# Baselli.net
KiCad netlist of a schematic drawn in EAGLE
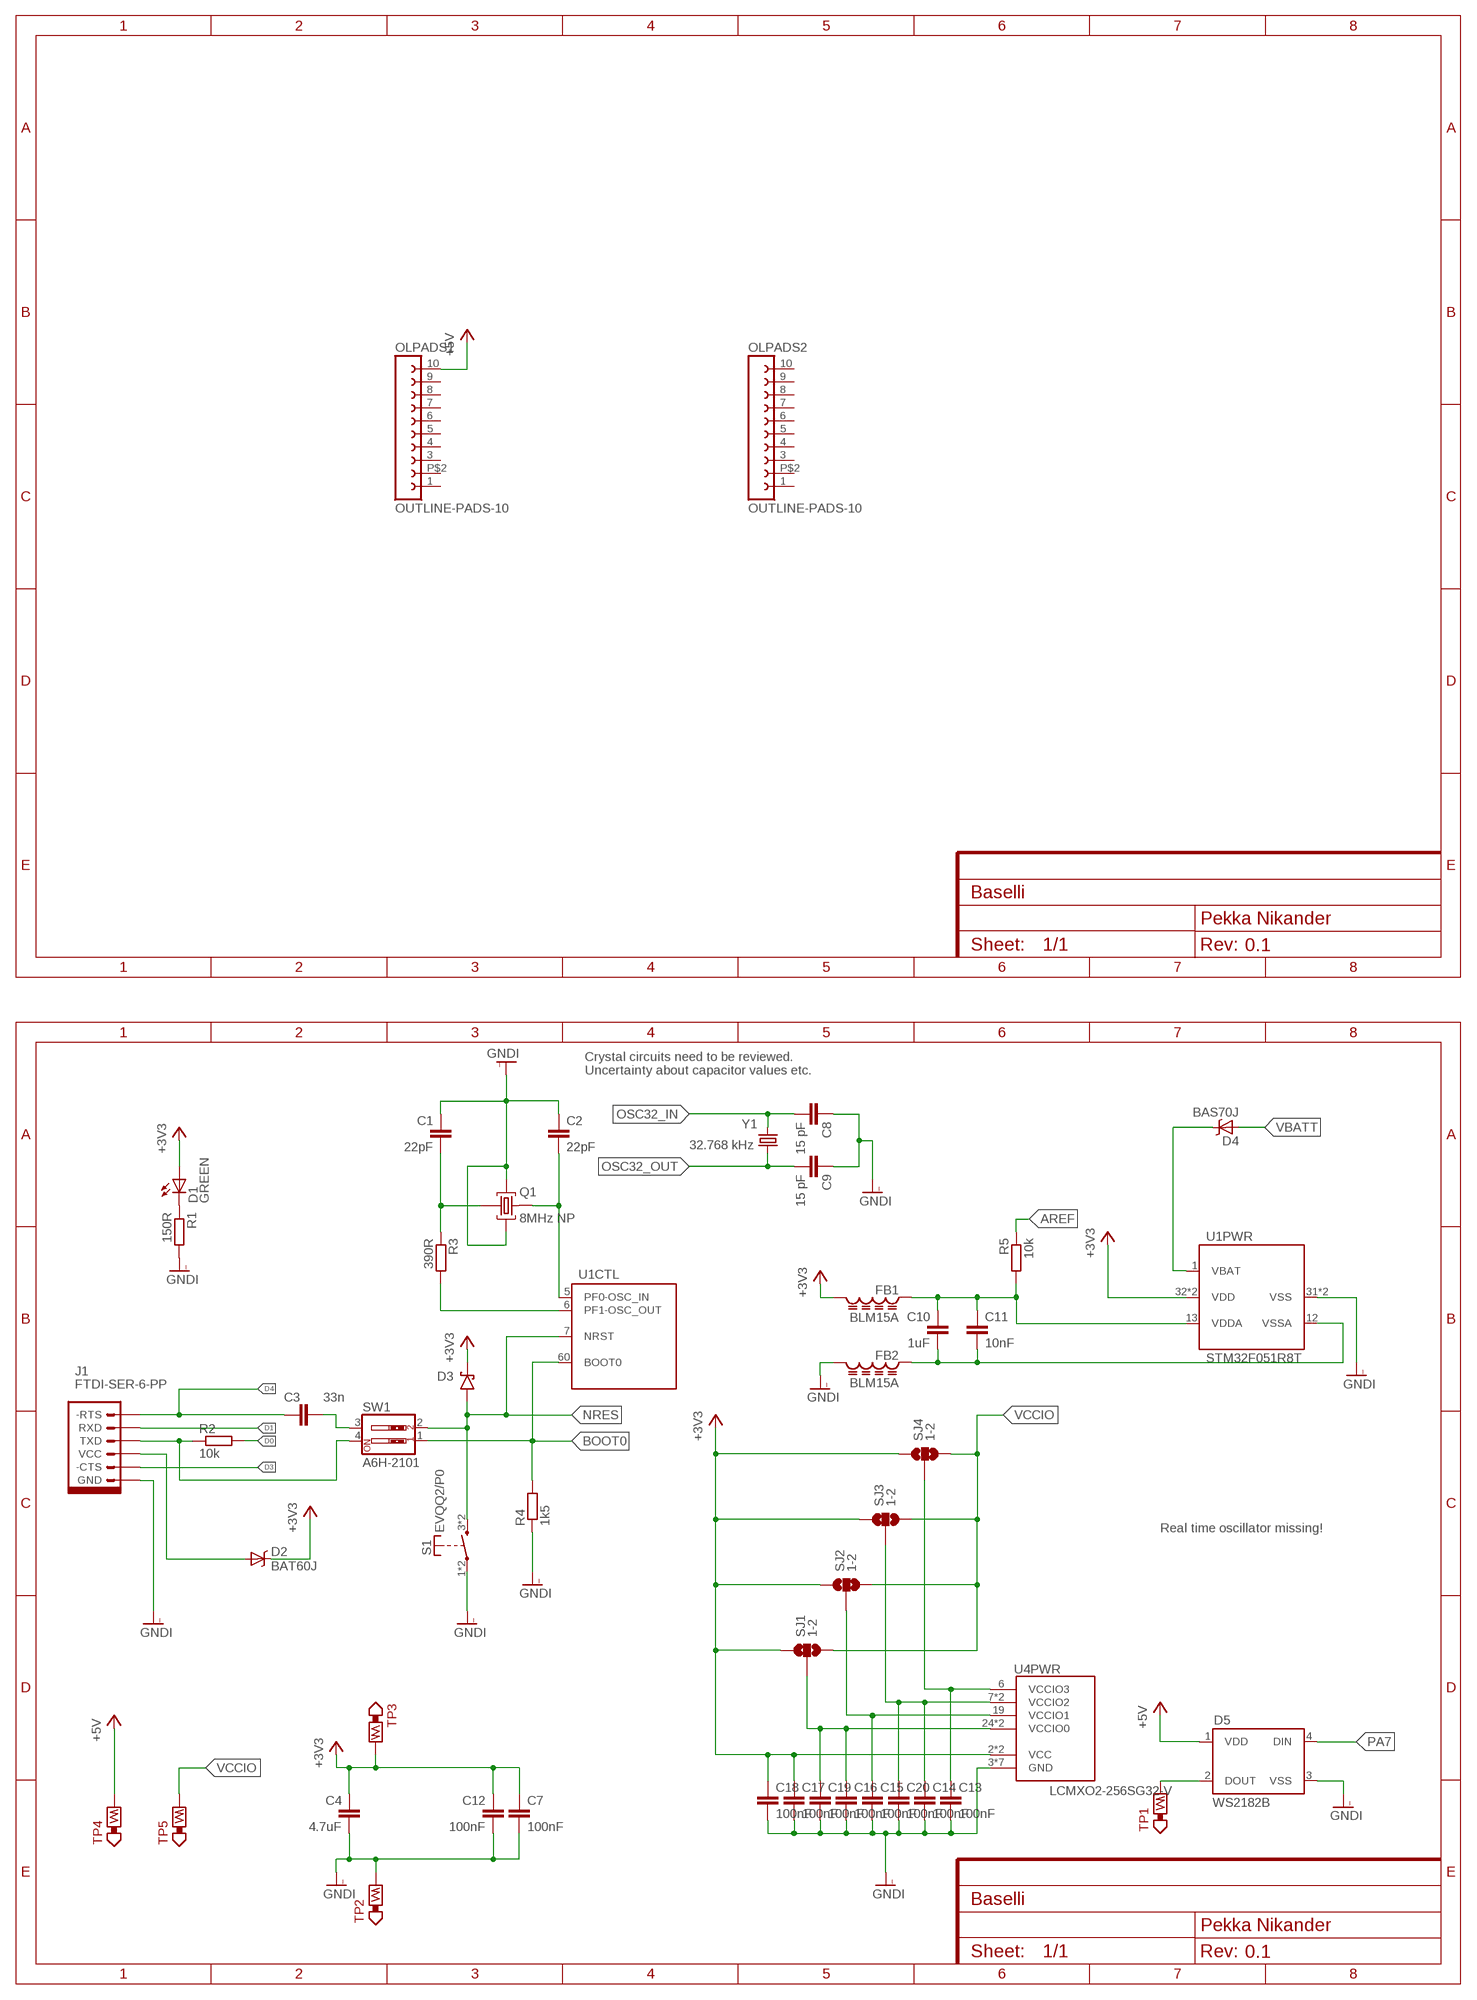
[diagram p0: schematic, sheet 1, part 1 of 2]
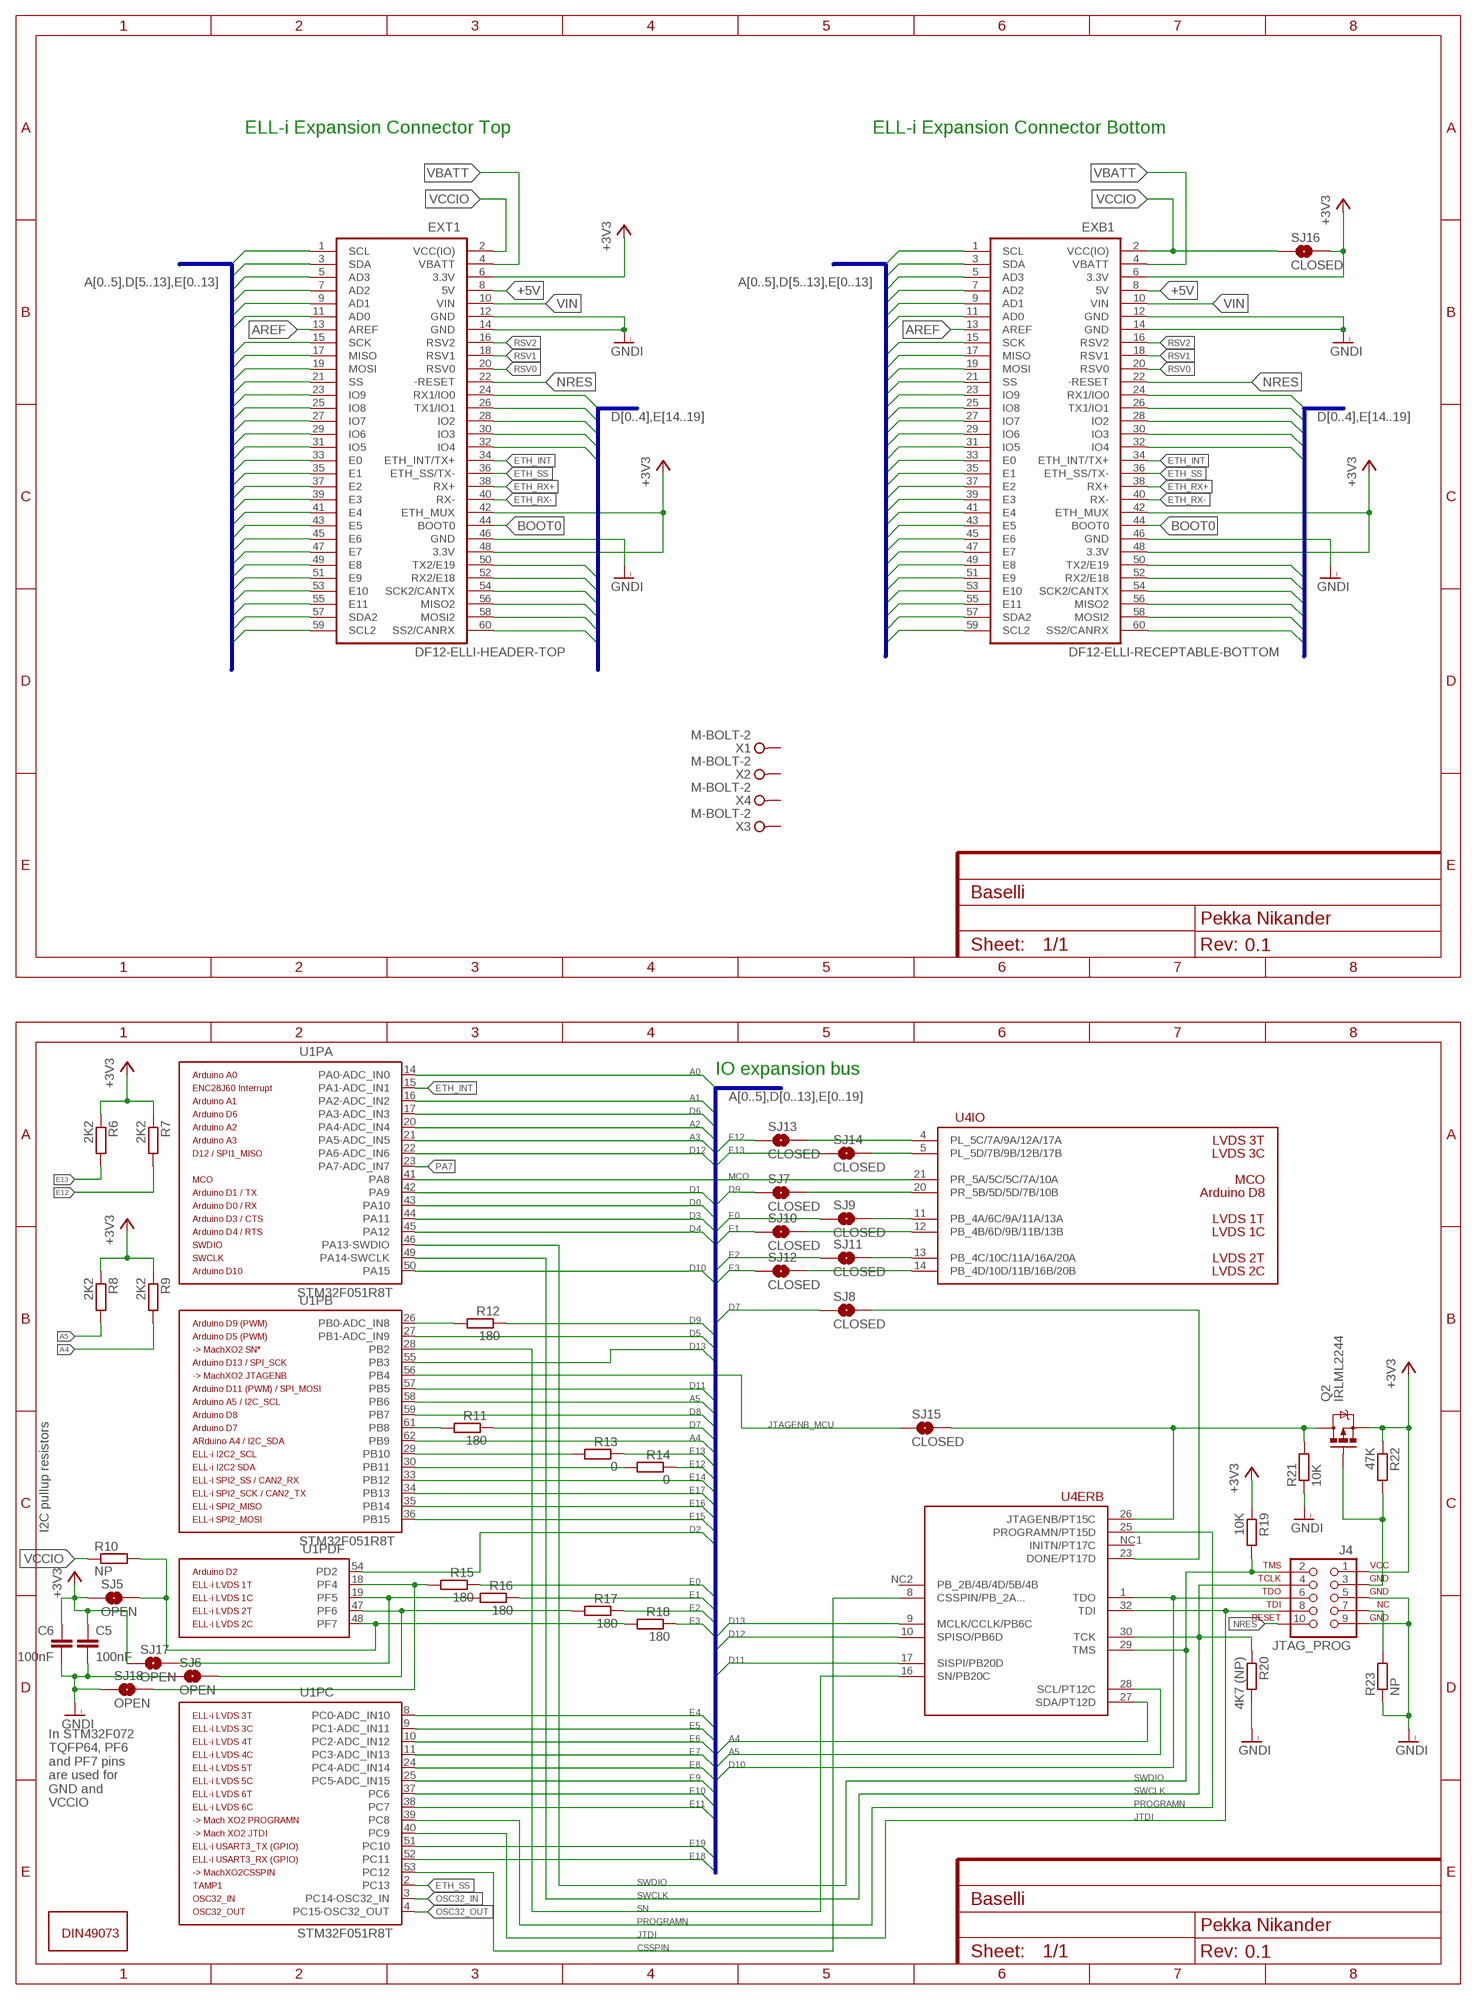
[diagram p1: schematic, sheet 1, part 2 of 2]

(export (version "E")
  (design (tool "Eeschema 10.0.6"))
  (components
    (comp (ref "C1")
      (value "22pF")
      (footprint "eagle-import:C0402")
      (libsource (lib "eagle-import") (part "C0402"))
    )
    (comp (ref "C2")
      (value "22pF")
      (footprint "eagle-import:C0402")
      (libsource (lib "eagle-import") (part "C0402"))
    )
    (comp (ref "C3")
      (value "33n")
      (footprint "eagle-import:C0402")
      (libsource (lib "eagle-import") (part "C0402"))
    )
    (comp (ref "C4")
      (value "4.7uF")
      (footprint "eagle-import:C0402")
      (libsource (lib "eagle-import") (part "C0402"))
    )
    (comp (ref "C5")
      (value "100nF")
      (footprint "eagle-import:C0402")
      (libsource (lib "eagle-import") (part "C0402"))
    )
    (comp (ref "C6")
      (value "100nF")
      (footprint "eagle-import:C0402")
      (libsource (lib "eagle-import") (part "C0402"))
    )
    (comp (ref "C7")
      (value "100nF")
      (footprint "eagle-import:C0402")
      (libsource (lib "eagle-import") (part "C0402"))
    )
    (comp (ref "C8")
      (value "15 pF")
      (footprint "eagle-import:C0402")
      (libsource (lib "eagle-import") (part "C0402"))
    )
    (comp (ref "C9")
      (value "15 pF")
      (footprint "eagle-import:C0402")
      (libsource (lib "eagle-import") (part "C0402"))
    )
    (comp (ref "C10")
      (value "1uF")
      (footprint "eagle-import:C0402")
      (libsource (lib "eagle-import") (part "C0402"))
    )
    (comp (ref "C11")
      (value "10nF")
      (footprint "eagle-import:C0402")
      (libsource (lib "eagle-import") (part "C0402"))
    )
    (comp (ref "C12")
      (value "100nF")
      (footprint "eagle-import:C0402")
      (libsource (lib "eagle-import") (part "C0402"))
    )
    (comp (ref "C13")
      (value "100nF")
      (footprint "eagle-import:C0402")
      (libsource (lib "eagle-import") (part "C0402"))
    )
    (comp (ref "C14")
      (value "100nF")
      (footprint "eagle-import:C0402")
      (libsource (lib "eagle-import") (part "C0402"))
    )
    (comp (ref "C15")
      (value "100nF")
      (footprint "eagle-import:C0402")
      (libsource (lib "eagle-import") (part "C0402"))
    )
    (comp (ref "C16")
      (value "100nF")
      (footprint "eagle-import:C0402")
      (libsource (lib "eagle-import") (part "C0402"))
    )
    (comp (ref "C17")
      (value "100nF")
      (footprint "eagle-import:C0402")
      (libsource (lib "eagle-import") (part "C0402"))
    )
    (comp (ref "C18")
      (value "100nF")
      (footprint "eagle-import:C0402")
      (libsource (lib "eagle-import") (part "C0402"))
    )
    (comp (ref "C19")
      (value "100nF")
      (footprint "eagle-import:C0402")
      (libsource (lib "eagle-import") (part "C0402"))
    )
    (comp (ref "C20")
      (value "100nF")
      (footprint "eagle-import:C0402")
      (libsource (lib "eagle-import") (part "C0402"))
    )
    (comp (ref "D1")
      (value "GREEN")
      (footprint "eagle-import:LED-0603")
      (libsource (lib "eagle-import") (part "LED-GREEN0603"))
    )
    (comp (ref "D2")
      (value "BAT60J")
      (footprint "eagle-import:SOD-323")
      (libsource (lib "eagle-import") (part "DIODE-SCHOTTKY-BAT60J"))
    )
    (comp (ref "D3")
      (value "BAT60J")
      (footprint "eagle-import:SOD323_DIODE")
      (libsource (lib "eagle-import") (part "BAT60J"))
    )
    (comp (ref "D4")
      (value "BAS70J")
      (footprint "eagle-import:SOD-323")
      (libsource (lib "eagle-import") (part "BAS70J"))
    )
    (comp (ref "D5")
      (value "WS2182B")
      (footprint "eagle-import:WS2812B")
      (libsource (lib "eagle-import") (part "WS2812B"))
    )
    (comp (ref "DIMENSIONS1")
      (value "DIN49073-OUTLINE")
      (footprint "eagle-import:DIN49073-1_2010-02-OUTLINE")
      (libsource (lib "eagle-import") (part "DIN49073-OUTLINE"))
    )
    (comp (ref "EXB1")
      (value "DF12-ELLI-RECEPTABLE-BOTTOM")
      (footprint "eagle-import:DF12-60DS-0.5V")
      (libsource (lib "eagle-import") (part "DF12-ELLI-RECEPTABLE-BOTTOM"))
    )
    (comp (ref "EXT1")
      (value "DF12-ELLI-HEADER-TOP")
      (footprint "eagle-import:DF12(4.0)-60DP-0.5V")
      (libsource (lib "eagle-import") (part "DF12-ELLI-HEADER-TOP"))
    )
    (comp (ref "FB1")
      (value "BLM15A")
      (footprint "eagle-import:0402")
      (libsource (lib "eagle-import") (part "LQM15"))
    )
    (comp (ref "FB2")
      (value "BLM15A")
      (footprint "eagle-import:0402")
      (libsource (lib "eagle-import") (part "LQM15"))
    )
    (comp (ref "J1")
      (value "FTDI-SER-6-PP")
      (footprint "eagle-import:FTDI-SER-6-SIL")
      (libsource (lib "eagle-import") (part "FTDI-SER-6-PP"))
    )
    (comp (ref "J4")
      (value "JTAG_PROG")
      (footprint "eagle-import:CLP-105-02-X-D")
      (libsource (lib "eagle-import") (part "JTAG_PROG"))
    )
    (comp (ref "OLPADS1")
      (value "OUTLINE-PADS-10")
      (footprint "eagle-import:DIN49073-1_2010-02-PADS-10")
      (libsource (lib "eagle-import") (part "OUTLINE-PADS-10"))
    )
    (comp (ref "OLPADS2")
      (value "OUTLINE-PADS-10")
      (footprint "eagle-import:DIN49073-1_2010-02-PADS-10")
      (libsource (lib "eagle-import") (part "OUTLINE-PADS-10"))
    )
    (comp (ref "Q1")
      (value "8MHz NP")
      (footprint "eagle-import:CRYSTAL-SMD-3225-GND")
      (libsource (lib "eagle-import") (part "CRYSTAL_WITH_GND"))
    )
    (comp (ref "Q2")
      (value "IRLML2244")
      (footprint "eagle-import:SOT23-3")
      (libsource (lib "eagle-import") (part "MOSFET-PCHANNELIRLML2244"))
    )
    (comp (ref "R1")
      (value "150R")
      (footprint "eagle-import:R0402")
      (libsource (lib "eagle-import") (part "R0402"))
    )
    (comp (ref "R2")
      (value "10k")
      (footprint "eagle-import:R0402")
      (libsource (lib "eagle-import") (part "R0402"))
    )
    (comp (ref "R3")
      (value "390R")
      (footprint "eagle-import:R0402")
      (libsource (lib "eagle-import") (part "R0402"))
    )
    (comp (ref "R4")
      (value "1k5")
      (footprint "eagle-import:R0402")
      (libsource (lib "eagle-import") (part "R0402"))
    )
    (comp (ref "R5")
      (value "10k")
      (footprint "eagle-import:R0805")
      (libsource (lib "eagle-import") (part "R0805"))
    )
    (comp (ref "R6")
      (value "2K2")
      (footprint "eagle-import:R0402")
      (libsource (lib "eagle-import") (part "R0402"))
    )
    (comp (ref "R7")
      (value "2K2")
      (footprint "eagle-import:R0402")
      (libsource (lib "eagle-import") (part "R0402"))
    )
    (comp (ref "R8")
      (value "2K2")
      (footprint "eagle-import:R0402")
      (libsource (lib "eagle-import") (part "R0402"))
    )
    (comp (ref "R9")
      (value "2K2")
      (footprint "eagle-import:R0402")
      (libsource (lib "eagle-import") (part "R0402"))
    )
    (comp (ref "R10")
      (value "NP")
      (footprint "eagle-import:R0805")
      (libsource (lib "eagle-import") (part "R0805"))
    )
    (comp (ref "R11")
      (value "180")
      (footprint "eagle-import:R0805")
      (libsource (lib "eagle-import") (part "R0805"))
    )
    (comp (ref "R12")
      (value "180")
      (footprint "eagle-import:R0805")
      (libsource (lib "eagle-import") (part "R0805"))
    )
    (comp (ref "R13")
      (value "0")
      (footprint "eagle-import:R0805")
      (libsource (lib "eagle-import") (part "R0805"))
    )
    (comp (ref "R14")
      (value "0")
      (footprint "eagle-import:R0805")
      (libsource (lib "eagle-import") (part "R0805"))
    )
    (comp (ref "R15")
      (value "180")
      (footprint "eagle-import:R0805")
      (libsource (lib "eagle-import") (part "R0805"))
    )
    (comp (ref "R16")
      (value "180")
      (footprint "eagle-import:R0805")
      (libsource (lib "eagle-import") (part "R0805"))
    )
    (comp (ref "R17")
      (value "180")
      (footprint "eagle-import:R0805")
      (libsource (lib "eagle-import") (part "R0805"))
    )
    (comp (ref "R18")
      (value "180")
      (footprint "eagle-import:R0805")
      (libsource (lib "eagle-import") (part "R0805"))
    )
    (comp (ref "R19")
      (value "10K")
      (footprint "eagle-import:R0402")
      (libsource (lib "eagle-import") (part "R0402"))
    )
    (comp (ref "R20")
      (value "4K7 (NP)")
      (footprint "eagle-import:R0603")
      (libsource (lib "eagle-import") (part "R0603"))
    )
    (comp (ref "R21")
      (value "10K")
      (footprint "eagle-import:R0402")
      (libsource (lib "eagle-import") (part "R0402"))
    )
    (comp (ref "R22")
      (value "47K")
      (footprint "eagle-import:R0402")
      (libsource (lib "eagle-import") (part "R0402"))
    )
    (comp (ref "R23")
      (value "NP")
      (footprint "eagle-import:R0805")
      (libsource (lib "eagle-import") (part "R0805"))
    )
    (comp (ref "S1")
      (value "EVQQ2/P0")
      (footprint "eagle-import:EVQQ2_P0")
      (libsource (lib "eagle-import") (part "EVQQ2/P0"))
    )
    (comp (ref "SJ1")
      (value "1-2")
      (footprint "eagle-import:SJ_3_PASTE1&2")
      (libsource (lib "eagle-import") (part "SOLDERJUMPER_2WAYPASTE1&2"))
    )
    (comp (ref "SJ2")
      (value "1-2")
      (footprint "eagle-import:SJ_3_PASTE1&2")
      (libsource (lib "eagle-import") (part "SOLDERJUMPER_2WAYPASTE1&2"))
    )
    (comp (ref "SJ3")
      (value "1-2")
      (footprint "eagle-import:SJ_3_PASTE1&2")
      (libsource (lib "eagle-import") (part "SOLDERJUMPER_2WAYPASTE1&2"))
    )
    (comp (ref "SJ4")
      (value "1-2")
      (footprint "eagle-import:SJ_3_PASTE1&2")
      (libsource (lib "eagle-import") (part "SOLDERJUMPER_2WAYPASTE1&2"))
    )
    (comp (ref "SJ5")
      (value "OPEN")
      (footprint "eagle-import:SJ_2S-NO")
      (libsource (lib "eagle-import") (part "SOLDERJUMPERNO"))
    )
    (comp (ref "SJ6")
      (value "OPEN")
      (footprint "eagle-import:SJ_2S-NO")
      (libsource (lib "eagle-import") (part "SOLDERJUMPERNO"))
    )
    (comp (ref "SJ7")
      (value "CLOSED")
      (footprint "eagle-import:SJ_2S-TRACE")
      (libsource (lib "eagle-import") (part "SOLDERJUMPERTRACE"))
    )
    (comp (ref "SJ8")
      (value "CLOSED")
      (footprint "eagle-import:SJ_2S-TRACE")
      (libsource (lib "eagle-import") (part "SOLDERJUMPERTRACE"))
    )
    (comp (ref "SJ9")
      (value "CLOSED")
      (footprint "eagle-import:SJ_2S-TRACE")
      (libsource (lib "eagle-import") (part "SOLDERJUMPERTRACE"))
    )
    (comp (ref "SJ10")
      (value "CLOSED")
      (footprint "eagle-import:SJ_2S-TRACE")
      (libsource (lib "eagle-import") (part "SOLDERJUMPERTRACE"))
    )
    (comp (ref "SJ11")
      (value "CLOSED")
      (footprint "eagle-import:SJ_2S-TRACE")
      (libsource (lib "eagle-import") (part "SOLDERJUMPERTRACE"))
    )
    (comp (ref "SJ12")
      (value "CLOSED")
      (footprint "eagle-import:SJ_2S-TRACE")
      (libsource (lib "eagle-import") (part "SOLDERJUMPERTRACE"))
    )
    (comp (ref "SJ13")
      (value "CLOSED")
      (footprint "eagle-import:SJ_2S-TRACE")
      (libsource (lib "eagle-import") (part "SOLDERJUMPERTRACE"))
    )
    (comp (ref "SJ14")
      (value "CLOSED")
      (footprint "eagle-import:SJ_2S-TRACE")
      (libsource (lib "eagle-import") (part "SOLDERJUMPERTRACE"))
    )
    (comp (ref "SJ15")
      (value "CLOSED")
      (footprint "eagle-import:SJ_2S-TRACE")
      (libsource (lib "eagle-import") (part "SOLDERJUMPERTRACE"))
    )
    (comp (ref "SJ16")
      (value "CLOSED")
      (footprint "eagle-import:SJ_2S-TRACE")
      (libsource (lib "eagle-import") (part "SOLDERJUMPERTRACE"))
    )
    (comp (ref "SJ17")
      (value "OPEN")
      (footprint "eagle-import:SJ_2S-NO")
      (libsource (lib "eagle-import") (part "SOLDERJUMPERNO"))
    )
    (comp (ref "SJ18")
      (value "OPEN")
      (footprint "eagle-import:SJ_2S-NO")
      (libsource (lib "eagle-import") (part "SOLDERJUMPERNO"))
    )
    (comp (ref "SW1")
      (value "A6H-2101")
      (footprint "eagle-import:DIPSWITCH-02-50MIL")
      (libsource (lib "eagle-import") (part "SW_DIP-2-SMT-HALFSIZE"))
    )
    (comp (ref "TP1")
      (value "TEST_POINT-5000")
      (footprint "eagle-import:TP_5021")
      (libsource (lib "eagle-import") (part "TEST_POINT-5000"))
    )
    (comp (ref "TP2")
      (value "TEST_POINT-5000")
      (footprint "eagle-import:TP_5021")
      (libsource (lib "eagle-import") (part "TEST_POINT-5000"))
    )
    (comp (ref "TP3")
      (value "TEST_POINT-5000")
      (footprint "eagle-import:TP_5021")
      (libsource (lib "eagle-import") (part "TEST_POINT-5000"))
    )
    (comp (ref "TP4")
      (value "TEST_POINT-5000")
      (footprint "eagle-import:TP_5021")
      (libsource (lib "eagle-import") (part "TEST_POINT-5000"))
    )
    (comp (ref "TP5")
      (value "TEST_POINT-5000")
      (footprint "eagle-import:TP_5021")
      (libsource (lib "eagle-import") (part "TEST_POINT-5000"))
    )
    (comp (ref "U1")
      (value "STM32F051R8T")
      (footprint "eagle-import:LQFP64")
      (libsource (lib "eagle-import") (part "STM32F051RT8"))
    )
    (comp (ref "U4")
      (value "LCMXO2-256SG32-V")
      (footprint "eagle-import:QFN-32-PAD-VIAS")
      (libsource (lib "eagle-import") (part "LCMXO2-256SG32-V"))
    )
    (comp (ref "X1")
      (value "M-BOLT-2")
      (footprint "eagle-import:M2-1")
      (libsource (lib "eagle-import") (part "M-BOLT-2"))
    )
    (comp (ref "X2")
      (value "M-BOLT-2")
      (footprint "eagle-import:M2-1")
      (libsource (lib "eagle-import") (part "M-BOLT-2"))
    )
    (comp (ref "X3")
      (value "M-BOLT-2")
      (footprint "eagle-import:M2-1")
      (libsource (lib "eagle-import") (part "M-BOLT-2"))
    )
    (comp (ref "X4")
      (value "M-BOLT-2")
      (footprint "eagle-import:M2-1")
      (libsource (lib "eagle-import") (part "M-BOLT-2"))
    )
    (comp (ref "Y1")
      (value "32.768 kHz")
      (footprint "eagle-import:CRYSTAL-32KHZ-SMD")
      (libsource (lib "eagle-import") (part "CRYSTAL32-SMD"))
    )
  )
  (nets
    (net (code "1") (name "+3V3") (class "Default")
      (node (ref "C12") (pin "1") (pinfunction "1_1") (pintype "passive"))
      (node (ref "C17") (pin "1") (pinfunction "1_1") (pintype "passive"))
      (node (ref "C18") (pin "1") (pinfunction "1_1") (pintype "passive"))
      (node (ref "C4") (pin "1") (pinfunction "1_1") (pintype "passive"))
      (node (ref "C5") (pin "1") (pinfunction "1_1") (pintype "passive"))
      (node (ref "C6") (pin "1") (pinfunction "1_1") (pintype "passive"))
      (node (ref "C7") (pin "1") (pinfunction "1_1") (pintype "passive"))
      (node (ref "D1") (pin "A") (pinfunction "A_A") (pintype "passive"))
      (node (ref "D2") (pin "C") (pinfunction "C_C") (pintype "passive"))
      (node (ref "D3") (pin "1") (pinfunction "C_1") (pintype "passive"))
      (node (ref "EXB1") (pin "42") (pinfunction "ETH_MUX_42") (pintype "bidirectional"))
      (node (ref "EXB1") (pin "48") (pinfunction "3.3V_48") (pintype "bidirectional"))
      (node (ref "EXB1") (pin "6") (pinfunction "3.3V_6") (pintype "power_in"))
      (node (ref "EXT1") (pin "42") (pinfunction "ETH_MUX_42") (pintype "bidirectional"))
      (node (ref "EXT1") (pin "48") (pinfunction "3.3V_48") (pintype "bidirectional"))
      (node (ref "EXT1") (pin "6") (pinfunction "3.3V_6") (pintype "power_in"))
      (node (ref "FB1") (pin "2") (pinfunction "2_2") (pintype "passive"))
      (node (ref "J4") (pin "1") (pinfunction "1_1") (pintype "power_in"))
      (node (ref "Q2") (pin "2") (pinfunction "S_2") (pintype "passive"))
      (node (ref "R19") (pin "1") (pinfunction "1_1") (pintype "passive"))
      (node (ref "R22") (pin "1") (pinfunction "1_1") (pintype "passive"))
      (node (ref "R6") (pin "1") (pinfunction "1_1") (pintype "passive"))
      (node (ref "R7") (pin "1") (pinfunction "1_1") (pintype "passive"))
      (node (ref "R8") (pin "1") (pinfunction "1_1") (pintype "passive"))
      (node (ref "R9") (pin "1") (pinfunction "1_1") (pintype "passive"))
      (node (ref "SJ1") (pin "1") (pinfunction "1_1") (pintype "passive"))
      (node (ref "SJ16") (pin "2") (pinfunction "2_2") (pintype "passive"))
      (node (ref "SJ17") (pin "1") (pinfunction "1_1") (pintype "passive"))
      (node (ref "SJ2") (pin "1") (pinfunction "1_1") (pintype "passive"))
      (node (ref "SJ3") (pin "1") (pinfunction "1_1") (pintype "passive"))
      (node (ref "SJ4") (pin "1") (pinfunction "1_1") (pintype "passive"))
      (node (ref "SJ5") (pin "1") (pinfunction "1_1") (pintype "passive"))
      (node (ref "TP3") (pin "P$1") (pinfunction "P$1_P$1") (pintype "passive"))
      (node (ref "U1") (pin "32") (pinfunction "VDD_32") (pintype "power_in"))
      (node (ref "U1") (pin "64") (pinfunction "VDD_64") (pintype "power_in"))
      (node (ref "U4") (pin "18") (pinfunction "VCC_18") (pintype "bidirectional"))
      (node (ref "U4") (pin "2") (pinfunction "VCC_2") (pintype "bidirectional"))
    )
    (net (code "2") (name "+5V") (class "Default")
      (node (ref "D5") (pin "1") (pinfunction "VDD_1") (pintype "power_in"))
      (node (ref "EXB1") (pin "8") (pinfunction "5V_8") (pintype "power_in"))
      (node (ref "EXT1") (pin "8") (pinfunction "5V_8") (pintype "power_in"))
      (node (ref "OLPADS1") (pin "10") (pinfunction "10_10") (pintype "passive"))
      (node (ref "TP4") (pin "P$1") (pinfunction "P$1_P$1") (pintype "passive"))
    )
    (net (code "3") (name "/A0") (class "Default")
      (node (ref "EXB1") (pin "11") (pinfunction "AD0_11") (pintype "passive"))
      (node (ref "EXT1") (pin "11") (pinfunction "AD0_11") (pintype "passive"))
      (node (ref "U1") (pin "14") (pinfunction "PA0-ADC_IN0_14") (pintype "bidirectional"))
    )
    (net (code "4") (name "/A1") (class "Default")
      (node (ref "EXB1") (pin "9") (pinfunction "AD1_9") (pintype "passive"))
      (node (ref "EXT1") (pin "9") (pinfunction "AD1_9") (pintype "passive"))
      (node (ref "U1") (pin "16") (pinfunction "PA2-ADC_IN2_16") (pintype "bidirectional"))
    )
    (net (code "5") (name "/A2") (class "Default")
      (node (ref "EXB1") (pin "7") (pinfunction "AD2_7") (pintype "passive"))
      (node (ref "EXT1") (pin "7") (pinfunction "AD2_7") (pintype "passive"))
      (node (ref "U1") (pin "20") (pinfunction "PA4-ADC_IN4_20") (pintype "bidirectional"))
    )
    (net (code "6") (name "/A3") (class "Default")
      (node (ref "EXB1") (pin "5") (pinfunction "AD3_5") (pintype "passive"))
      (node (ref "EXT1") (pin "5") (pinfunction "AD3_5") (pintype "passive"))
      (node (ref "U1") (pin "21") (pinfunction "PA5-ADC_IN5_21") (pintype "bidirectional"))
    )
    (net (code "7") (name "/CSSPIN") (class "Default")
      (node (ref "U1") (pin "53") (pinfunction "PC12_53") (pintype "bidirectional"))
      (node (ref "U4") (pin "8") (pinfunction "CSSPIN/PB_2A..._8") (pintype "bidirectional"))
    )
    (net (code "8") (name "/D2") (class "Default")
      (node (ref "EXB1") (pin "28") (pinfunction "IO2_28") (pintype "bidirectional"))
      (node (ref "EXT1") (pin "28") (pinfunction "IO2_28") (pintype "bidirectional"))
      (node (ref "U1") (pin "54") (pinfunction "PD2_54") (pintype "bidirectional"))
    )
    (net (code "9") (name "/D5") (class "Default")
      (node (ref "EXB1") (pin "31") (pinfunction "IO5_31") (pintype "bidirectional"))
      (node (ref "EXT1") (pin "31") (pinfunction "IO5_31") (pintype "bidirectional"))
      (node (ref "U1") (pin "27") (pinfunction "PB1-ADC_IN9_27") (pintype "bidirectional"))
    )
    (net (code "10") (name "/D6") (class "Default")
      (node (ref "EXB1") (pin "29") (pinfunction "IO6_29") (pintype "bidirectional"))
      (node (ref "EXT1") (pin "29") (pinfunction "IO6_29") (pintype "bidirectional"))
      (node (ref "U1") (pin "17") (pinfunction "PA3-ADC_IN3_17") (pintype "bidirectional"))
    )
    (net (code "11") (name "/D7") (class "Default")
      (node (ref "EXB1") (pin "27") (pinfunction "IO7_27") (pintype "bidirectional"))
      (node (ref "EXT1") (pin "27") (pinfunction "IO7_27") (pintype "bidirectional"))
      (node (ref "R11") (pin "1") (pinfunction "1_1") (pintype "passive"))
      (node (ref "SJ8") (pin "1") (pinfunction "1_1") (pintype "passive"))
    )
    (net (code "12") (name "/D8") (class "Default")
      (node (ref "EXB1") (pin "25") (pinfunction "IO8_25") (pintype "bidirectional"))
      (node (ref "EXT1") (pin "25") (pinfunction "IO8_25") (pintype "bidirectional"))
      (node (ref "U1") (pin "59") (pinfunction "PB7_59") (pintype "bidirectional"))
    )
    (net (code "13") (name "/D9") (class "Default")
      (node (ref "EXB1") (pin "23") (pinfunction "IO9_23") (pintype "bidirectional"))
      (node (ref "EXT1") (pin "23") (pinfunction "IO9_23") (pintype "bidirectional"))
      (node (ref "R12") (pin "1") (pinfunction "1_1") (pintype "passive"))
      (node (ref "SJ7") (pin "1") (pinfunction "1_1") (pintype "passive"))
    )
    (net (code "14") (name "/D10") (class "Default")
      (node (ref "EXB1") (pin "21") (pinfunction "SS_21") (pintype "bidirectional"))
      (node (ref "EXT1") (pin "21") (pinfunction "SS_21") (pintype "bidirectional"))
      (node (ref "J4") (pin "6") (pinfunction "6_6") (pintype "bidirectional"))
      (node (ref "U1") (pin "50") (pinfunction "PA15_50") (pintype "bidirectional"))
      (node (ref "U4") (pin "1") (pinfunction "TDO_1") (pintype "bidirectional"))
    )
    (net (code "15") (name "/D11") (class "Default")
      (node (ref "EXB1") (pin "19") (pinfunction "MOSI_19") (pintype "bidirectional"))
      (node (ref "EXT1") (pin "19") (pinfunction "MOSI_19") (pintype "bidirectional"))
      (node (ref "U1") (pin "57") (pinfunction "PB5_57") (pintype "bidirectional"))
      (node (ref "U4") (pin "17") (pinfunction "SISPI/PB20D_17") (pintype "bidirectional"))
    )
    (net (code "16") (name "/D12") (class "Default")
      (node (ref "EXB1") (pin "17") (pinfunction "MISO_17") (pintype "bidirectional"))
      (node (ref "EXT1") (pin "17") (pinfunction "MISO_17") (pintype "bidirectional"))
      (node (ref "U1") (pin "22") (pinfunction "PA6-ADC_IN6_22") (pintype "bidirectional"))
      (node (ref "U4") (pin "10") (pinfunction "SPISO/PB6D_10") (pintype "bidirectional"))
    )
    (net (code "17") (name "/D13") (class "Default")
      (node (ref "EXB1") (pin "15") (pinfunction "SCK_15") (pintype "bidirectional"))
      (node (ref "EXT1") (pin "15") (pinfunction "SCK_15") (pintype "bidirectional"))
      (node (ref "U1") (pin "55") (pinfunction "PB3_55") (pintype "bidirectional"))
      (node (ref "U4") (pin "9") (pinfunction "MCLK/CCLK/PB6C_9") (pintype "bidirectional"))
    )
    (net (code "18") (name "/E0") (class "Default")
      (node (ref "EXB1") (pin "33") (pinfunction "E0_33") (pintype "bidirectional"))
      (node (ref "EXT1") (pin "33") (pinfunction "E0_33") (pintype "bidirectional"))
      (node (ref "R15") (pin "1") (pinfunction "1_1") (pintype "passive"))
      (node (ref "SJ9") (pin "1") (pinfunction "1_1") (pintype "passive"))
    )
    (net (code "19") (name "/E1") (class "Default")
      (node (ref "EXB1") (pin "35") (pinfunction "E1_35") (pintype "bidirectional"))
      (node (ref "EXT1") (pin "35") (pinfunction "E1_35") (pintype "bidirectional"))
      (node (ref "R16") (pin "1") (pinfunction "1_1") (pintype "passive"))
      (node (ref "SJ10") (pin "1") (pinfunction "1_1") (pintype "passive"))
    )
    (net (code "20") (name "/E2") (class "Default")
      (node (ref "EXB1") (pin "37") (pinfunction "E2_37") (pintype "bidirectional"))
      (node (ref "EXT1") (pin "37") (pinfunction "E2_37") (pintype "bidirectional"))
      (node (ref "R17") (pin "1") (pinfunction "1_1") (pintype "passive"))
      (node (ref "SJ11") (pin "1") (pinfunction "1_1") (pintype "passive"))
    )
    (net (code "21") (name "/E3") (class "Default")
      (node (ref "EXB1") (pin "39") (pinfunction "E3_39") (pintype "bidirectional"))
      (node (ref "EXT1") (pin "39") (pinfunction "E3_39") (pintype "bidirectional"))
      (node (ref "R18") (pin "1") (pinfunction "1_1") (pintype "passive"))
      (node (ref "SJ12") (pin "1") (pinfunction "1_1") (pintype "passive"))
    )
    (net (code "22") (name "/E4") (class "Default")
      (node (ref "EXB1") (pin "41") (pinfunction "E4_41") (pintype "bidirectional"))
      (node (ref "EXT1") (pin "41") (pinfunction "E4_41") (pintype "bidirectional"))
      (node (ref "U1") (pin "8") (pinfunction "PC0-ADC_IN10_8") (pintype "bidirectional"))
    )
    (net (code "23") (name "/E5") (class "Default")
      (node (ref "EXB1") (pin "43") (pinfunction "E5_43") (pintype "bidirectional"))
      (node (ref "EXT1") (pin "43") (pinfunction "E5_43") (pintype "bidirectional"))
      (node (ref "U1") (pin "9") (pinfunction "PC1-ADC_IN11_9") (pintype "bidirectional"))
    )
    (net (code "24") (name "/E6") (class "Default")
      (node (ref "EXB1") (pin "45") (pinfunction "E6_45") (pintype "bidirectional"))
      (node (ref "EXT1") (pin "45") (pinfunction "E6_45") (pintype "bidirectional"))
      (node (ref "U1") (pin "10") (pinfunction "PC2-ADC_IN12_10") (pintype "bidirectional"))
    )
    (net (code "25") (name "/E7") (class "Default")
      (node (ref "EXB1") (pin "47") (pinfunction "E7_47") (pintype "bidirectional"))
      (node (ref "EXT1") (pin "47") (pinfunction "E7_47") (pintype "bidirectional"))
      (node (ref "U1") (pin "11") (pinfunction "PC3-ADC_IN13_11") (pintype "bidirectional"))
    )
    (net (code "26") (name "/E8") (class "Default")
      (node (ref "EXB1") (pin "49") (pinfunction "E8_49") (pintype "bidirectional"))
      (node (ref "EXT1") (pin "49") (pinfunction "E8_49") (pintype "bidirectional"))
      (node (ref "U1") (pin "24") (pinfunction "PC4-ADC_IN14_24") (pintype "bidirectional"))
    )
    (net (code "27") (name "/E9") (class "Default")
      (node (ref "EXB1") (pin "51") (pinfunction "E9_51") (pintype "bidirectional"))
      (node (ref "EXT1") (pin "51") (pinfunction "E9_51") (pintype "bidirectional"))
      (node (ref "U1") (pin "25") (pinfunction "PC5-ADC_IN15_25") (pintype "bidirectional"))
    )
    (net (code "28") (name "/E10") (class "Default")
      (node (ref "EXB1") (pin "53") (pinfunction "E10_53") (pintype "bidirectional"))
      (node (ref "EXT1") (pin "53") (pinfunction "E10_53") (pintype "bidirectional"))
      (node (ref "U1") (pin "37") (pinfunction "PC6_37") (pintype "bidirectional"))
    )
    (net (code "29") (name "/E11") (class "Default")
      (node (ref "EXB1") (pin "55") (pinfunction "E11_55") (pintype "bidirectional"))
      (node (ref "EXT1") (pin "55") (pinfunction "E11_55") (pintype "bidirectional"))
      (node (ref "U1") (pin "38") (pinfunction "PC7_38") (pintype "bidirectional"))
    )
    (net (code "30") (name "/E14") (class "Default")
      (node (ref "EXB1") (pin "60") (pinfunction "SS2/CANRX_60") (pintype "bidirectional"))
      (node (ref "EXT1") (pin "60") (pinfunction "SS2/CANRX_60") (pintype "bidirectional"))
      (node (ref "U1") (pin "33") (pinfunction "PB12_33") (pintype "bidirectional"))
    )
    (net (code "31") (name "/E15") (class "Default")
      (node (ref "EXB1") (pin "58") (pinfunction "MOSI2_58") (pintype "bidirectional"))
      (node (ref "EXT1") (pin "58") (pinfunction "MOSI2_58") (pintype "bidirectional"))
      (node (ref "U1") (pin "36") (pinfunction "PB15_36") (pintype "bidirectional"))
    )
    (net (code "32") (name "/E16") (class "Default")
      (node (ref "EXB1") (pin "56") (pinfunction "MISO2_56") (pintype "bidirectional"))
      (node (ref "EXT1") (pin "56") (pinfunction "MISO2_56") (pintype "bidirectional"))
      (node (ref "U1") (pin "35") (pinfunction "PB14_35") (pintype "bidirectional"))
    )
    (net (code "33") (name "/E17") (class "Default")
      (node (ref "EXB1") (pin "54") (pinfunction "SCK2/CANTX_54") (pintype "bidirectional"))
      (node (ref "EXT1") (pin "54") (pinfunction "SCK2/CANTX_54") (pintype "bidirectional"))
      (node (ref "U1") (pin "34") (pinfunction "PB13_34") (pintype "bidirectional"))
    )
    (net (code "34") (name "/E18") (class "Default")
      (node (ref "EXB1") (pin "52") (pinfunction "RX2/E18_52") (pintype "bidirectional"))
      (node (ref "EXT1") (pin "52") (pinfunction "RX2/E18_52") (pintype "bidirectional"))
      (node (ref "U1") (pin "52") (pinfunction "PC11_52") (pintype "bidirectional"))
    )
    (net (code "35") (name "/E19") (class "Default")
      (node (ref "EXB1") (pin "50") (pinfunction "TX2/E19_50") (pintype "bidirectional"))
      (node (ref "EXT1") (pin "50") (pinfunction "TX2/E19_50") (pintype "bidirectional"))
      (node (ref "U1") (pin "51") (pinfunction "PC10_51") (pintype "bidirectional"))
    )
    (net (code "36") (name "/JTAGENB_MCU") (class "Default")
      (node (ref "SJ15") (pin "1") (pinfunction "1_1") (pintype "passive"))
      (node (ref "U1") (pin "56") (pinfunction "PB4_56") (pintype "bidirectional"))
    )
    (net (code "37") (name "/JTDI") (class "Default")
      (node (ref "J4") (pin "8") (pinfunction "8_8") (pintype "bidirectional"))
      (node (ref "U1") (pin "40") (pinfunction "PC9_40") (pintype "bidirectional"))
      (node (ref "U4") (pin "32") (pinfunction "TDI_32") (pintype "bidirectional"))
    )
    (net (code "38") (name "/MCO") (class "Default")
      (node (ref "U1") (pin "41") (pinfunction "PA8_41") (pintype "bidirectional"))
      (node (ref "U4") (pin "21") (pinfunction "PR_5A/5C/5C/7A/10A_21") (pintype "bidirectional"))
    )
    (net (code "39") (name "/PROGRAMN") (class "Default")
      (node (ref "U1") (pin "39") (pinfunction "PC8_39") (pintype "bidirectional"))
      (node (ref "U4") (pin "25") (pinfunction "PROGRAMN/PT15D_25") (pintype "bidirectional"))
    )
    (net (code "40") (name "/SN") (class "Default")
      (node (ref "U1") (pin "28") (pinfunction "PB2_28") (pintype "bidirectional"))
      (node (ref "U4") (pin "16") (pinfunction "SN/PB20C_16") (pintype "bidirectional"))
    )
    (net (code "41") (name "/SWCLK") (class "Default")
      (node (ref "J4") (pin "4") (pinfunction "4_4") (pintype "bidirectional"))
      (node (ref "R20") (pin "1") (pinfunction "1_1") (pintype "passive"))
      (node (ref "U1") (pin "49") (pinfunction "PA14-SWCLK_49") (pintype "bidirectional"))
      (node (ref "U4") (pin "30") (pinfunction "TCK_30") (pintype "bidirectional"))
    )
    (net (code "42") (name "/SWDIO") (class "Default")
      (node (ref "J4") (pin "2") (pinfunction "2_2") (pintype "bidirectional"))
      (node (ref "R19") (pin "2") (pinfunction "2_2") (pintype "passive"))
      (node (ref "U1") (pin "46") (pinfunction "PA13-SWDIO_46") (pintype "bidirectional"))
      (node (ref "U4") (pin "29") (pinfunction "TMS_29") (pintype "bidirectional"))
    )
    (net (code "46") (name "A4") (class "Default")
      (node (ref "EXB1") (pin "3") (pinfunction "SDA_3") (pintype "bidirectional"))
      (node (ref "EXT1") (pin "3") (pinfunction "SDA_3") (pintype "bidirectional"))
      (node (ref "R9") (pin "2") (pinfunction "2_2") (pintype "passive"))
      (node (ref "U1") (pin "62") (pinfunction "PB9_62") (pintype "bidirectional"))
      (node (ref "U4") (pin "27") (pinfunction "SDA/PT12D_27") (pintype "bidirectional"))
    )
    (net (code "47") (name "A5") (class "Default")
      (node (ref "EXB1") (pin "1") (pinfunction "SCL_1") (pintype "bidirectional"))
      (node (ref "EXT1") (pin "1") (pinfunction "SCL_1") (pintype "bidirectional"))
      (node (ref "R8") (pin "2") (pinfunction "2_2") (pintype "passive"))
      (node (ref "U1") (pin "58") (pinfunction "PB6_58") (pintype "bidirectional"))
      (node (ref "U4") (pin "28") (pinfunction "SCL/PT12C_28") (pintype "bidirectional"))
    )
    (net (code "48") (name "AREF") (class "Default")
      (node (ref "EXB1") (pin "13") (pinfunction "AREF_13") (pintype "passive"))
      (node (ref "EXT1") (pin "13") (pinfunction "AREF_13") (pintype "passive"))
      (node (ref "R5") (pin "1") (pinfunction "1_1") (pintype "passive"))
    )
    (net (code "49") (name "BOOT0") (class "Default")
      (node (ref "EXB1") (pin "44") (pinfunction "BOOT0_44") (pintype "bidirectional"))
      (node (ref "EXT1") (pin "44") (pinfunction "BOOT0_44") (pintype "bidirectional"))
      (node (ref "R4") (pin "2") (pinfunction "2_2") (pintype "passive"))
      (node (ref "SW1") (pin "1") (pinfunction "1_1") (pintype "passive"))
      (node (ref "U1") (pin "60") (pinfunction "BOOT0_60") (pintype "bidirectional"))
    )
    (net (code "50") (name "D0") (class "Default")
      (node (ref "EXB1") (pin "24") (pinfunction "RX1/IO0_24") (pintype "bidirectional"))
      (node (ref "EXT1") (pin "24") (pinfunction "RX1/IO0_24") (pintype "bidirectional"))
      (node (ref "R2") (pin "2") (pinfunction "2_2") (pintype "passive"))
      (node (ref "U1") (pin "43") (pinfunction "PA10_43") (pintype "bidirectional"))
    )
    (net (code "51") (name "D1") (class "Default")
      (node (ref "EXB1") (pin "26") (pinfunction "TX1/IO1_26") (pintype "bidirectional"))
      (node (ref "EXT1") (pin "26") (pinfunction "TX1/IO1_26") (pintype "bidirectional"))
      (node (ref "J1") (pin "RXD") (pinfunction "RXD_RXD") (pintype "passive"))
      (node (ref "U1") (pin "42") (pinfunction "PA9_42") (pintype "bidirectional"))
    )
    (net (code "52") (name "D3") (class "Default")
      (node (ref "EXB1") (pin "30") (pinfunction "IO3_30") (pintype "bidirectional"))
      (node (ref "EXT1") (pin "30") (pinfunction "IO3_30") (pintype "bidirectional"))
      (node (ref "J1") (pin "-CTS") (pinfunction "-CTS_-CTS") (pintype "passive"))
      (node (ref "U1") (pin "44") (pinfunction "PA11_44") (pintype "bidirectional"))
    )
    (net (code "53") (name "D4") (class "Default")
      (node (ref "C3") (pin "1") (pinfunction "1_1") (pintype "passive"))
      (node (ref "EXB1") (pin "32") (pinfunction "IO4_32") (pintype "bidirectional"))
      (node (ref "EXT1") (pin "32") (pinfunction "IO4_32") (pintype "bidirectional"))
      (node (ref "J1") (pin "-RTS") (pinfunction "-RTS_-RTS") (pintype "passive"))
      (node (ref "U1") (pin "45") (pinfunction "PA12_45") (pintype "bidirectional"))
    )
    (net (code "54") (name "E12") (class "Default")
      (node (ref "EXB1") (pin "57") (pinfunction "SDA2_57") (pintype "bidirectional"))
      (node (ref "EXT1") (pin "57") (pinfunction "SDA2_57") (pintype "bidirectional"))
      (node (ref "R14") (pin "1") (pinfunction "1_1") (pintype "passive"))
      (node (ref "R7") (pin "2") (pinfunction "2_2") (pintype "passive"))
      (node (ref "SJ13") (pin "1") (pinfunction "1_1") (pintype "passive"))
    )
    (net (code "55") (name "E13") (class "Default")
      (node (ref "EXB1") (pin "59") (pinfunction "SCL2_59") (pintype "bidirectional"))
      (node (ref "EXT1") (pin "59") (pinfunction "SCL2_59") (pintype "bidirectional"))
      (node (ref "R13") (pin "1") (pinfunction "1_1") (pintype "passive"))
      (node (ref "R6") (pin "2") (pinfunction "2_2") (pintype "passive"))
      (node (ref "SJ14") (pin "1") (pinfunction "1_1") (pintype "passive"))
    )
    (net (code "56") (name "ETH_INT") (class "Default")
      (node (ref "EXB1") (pin "34") (pinfunction "ETH_INT/TX+_34") (pintype "bidirectional"))
      (node (ref "EXT1") (pin "34") (pinfunction "ETH_INT/TX+_34") (pintype "bidirectional"))
      (node (ref "U1") (pin "15") (pinfunction "PA1-ADC_IN1_15") (pintype "bidirectional"))
    )
    (net (code "57") (name "ETH_RX+") (class "Default")
      (node (ref "EXB1") (pin "38") (pinfunction "RX+_38") (pintype "bidirectional"))
      (node (ref "EXT1") (pin "38") (pinfunction "RX+_38") (pintype "bidirectional"))
    )
    (net (code "58") (name "ETH_RX-") (class "Default")
      (node (ref "EXB1") (pin "40") (pinfunction "RX-_40") (pintype "bidirectional"))
      (node (ref "EXT1") (pin "40") (pinfunction "RX-_40") (pintype "bidirectional"))
    )
    (net (code "59") (name "ETH_SS") (class "Default")
      (node (ref "EXB1") (pin "36") (pinfunction "ETH_SS/TX-_36") (pintype "bidirectional"))
      (node (ref "EXT1") (pin "36") (pinfunction "ETH_SS/TX-_36") (pintype "bidirectional"))
      (node (ref "U1") (pin "2") (pinfunction "PC13_2") (pintype "bidirectional"))
    )
    (net (code "60") (name "GNDI") (class "Default")
      (node (ref "C1") (pin "1") (pinfunction "1_1") (pintype "passive"))
      (node (ref "C12") (pin "2") (pinfunction "2_2") (pintype "passive"))
      (node (ref "C13") (pin "2") (pinfunction "2_2") (pintype "passive"))
      (node (ref "C14") (pin "2") (pinfunction "2_2") (pintype "passive"))
      (node (ref "C15") (pin "2") (pinfunction "2_2") (pintype "passive"))
      (node (ref "C16") (pin "2") (pinfunction "2_2") (pintype "passive"))
      (node (ref "C17") (pin "2") (pinfunction "2_2") (pintype "passive"))
      (node (ref "C18") (pin "2") (pinfunction "2_2") (pintype "passive"))
      (node (ref "C19") (pin "2") (pinfunction "2_2") (pintype "passive"))
      (node (ref "C2") (pin "1") (pinfunction "1_1") (pintype "passive"))
      (node (ref "C20") (pin "2") (pinfunction "2_2") (pintype "passive"))
      (node (ref "C4") (pin "2") (pinfunction "2_2") (pintype "passive"))
      (node (ref "C5") (pin "2") (pinfunction "2_2") (pintype "passive"))
      (node (ref "C6") (pin "2") (pinfunction "2_2") (pintype "passive"))
      (node (ref "C7") (pin "2") (pinfunction "2_2") (pintype "passive"))
      (node (ref "C8") (pin "1") (pinfunction "1_1") (pintype "passive"))
      (node (ref "C9") (pin "1") (pinfunction "1_1") (pintype "passive"))
      (node (ref "D5") (pin "3") (pinfunction "VSS_3") (pintype "power_in"))
      (node (ref "EXB1") (pin "12") (pinfunction "GND_12") (pintype "power_in"))
      (node (ref "EXB1") (pin "14") (pinfunction "GND_14") (pintype "power_in"))
      (node (ref "EXB1") (pin "46") (pinfunction "GND_46") (pintype "bidirectional"))
      (node (ref "EXT1") (pin "12") (pinfunction "GND_12") (pintype "power_in"))
      (node (ref "EXT1") (pin "14") (pinfunction "GND_14") (pintype "power_in"))
      (node (ref "EXT1") (pin "46") (pinfunction "GND_46") (pintype "bidirectional"))
      (node (ref "FB2") (pin "2") (pinfunction "2_2") (pintype "passive"))
      (node (ref "J1") (pin "GND") (pinfunction "GND_GND") (pintype "passive"))
      (node (ref "J4") (pin "5") (pinfunction "5_5") (pintype "power_in"))
      (node (ref "J4") (pin "9") (pinfunction "9_9") (pintype "power_in"))
      (node (ref "Q1") (pin "2") (pinfunction "GND_2") (pintype "passive"))
      (node (ref "Q1") (pin "4") (pinfunction "GND_4") (pintype "passive"))
      (node (ref "R1") (pin "2") (pinfunction "2_2") (pintype "passive"))
      (node (ref "R20") (pin "2") (pinfunction "2_2") (pintype "passive"))
      (node (ref "R21") (pin "1") (pinfunction "1_1") (pintype "passive"))
      (node (ref "R23") (pin "1") (pinfunction "1_1") (pintype "passive"))
      (node (ref "R4") (pin "1") (pinfunction "1_1") (pintype "passive"))
      (node (ref "S1") (pin "1") (pinfunction "P_1") (pintype "passive"))
      (node (ref "S1") (pin "2") (pinfunction "P_2") (pintype "passive"))
      (node (ref "SJ18") (pin "1") (pinfunction "1_1") (pintype "passive"))
      (node (ref "SJ6") (pin "1") (pinfunction "1_1") (pintype "passive"))
      (node (ref "TP2") (pin "P$1") (pinfunction "P$1_P$1") (pintype "passive"))
      (node (ref "U1") (pin "31") (pinfunction "VSS_31") (pintype "power_in"))
      (node (ref "U1") (pin "63") (pinfunction "VSS_63") (pintype "power_in"))
      (node (ref "U4") (pin "22") (pinfunction "GND_22") (pintype "bidirectional"))
      (node (ref "U4") (pin "3") (pinfunction "GND_3") (pintype "bidirectional"))
      (node (ref "U4") (pin "EP") (pinfunction "GND_EP") (pintype "bidirectional"))
      (node (ref "U4") (pin "VIA1") (pinfunction "GND_VIA1") (pintype "bidirectional"))
      (node (ref "U4") (pin "VIA2") (pinfunction "GND_VIA2") (pintype "bidirectional"))
      (node (ref "U4") (pin "VIA3") (pinfunction "GND_VIA3") (pintype "bidirectional"))
      (node (ref "U4") (pin "VIA4") (pinfunction "GND_VIA4") (pintype "bidirectional"))
    )
    (net (code "61") (name "NRES") (class "Default")
      (node (ref "D3") (pin "2") (pinfunction "A_2") (pintype "passive"))
      (node (ref "EXB1") (pin "22") (pinfunction "-RESET_22") (pintype "bidirectional"))
      (node (ref "EXT1") (pin "22") (pinfunction "-RESET_22") (pintype "bidirectional"))
      (node (ref "J4") (pin "10") (pinfunction "10_10") (pintype "bidirectional"))
      (node (ref "S1") (pin "3") (pinfunction "S_3") (pintype "passive"))
      (node (ref "S1") (pin "4") (pinfunction "S_4") (pintype "passive"))
      (node (ref "SW1") (pin "2") (pinfunction "2_2") (pintype "passive"))
      (node (ref "U1") (pin "7") (pinfunction "NRST_7") (pintype "bidirectional"))
    )
    (net (code "62") (name "Net-(C3-Pad2)") (class "Default")
      (node (ref "C3") (pin "2") (pinfunction "2_2") (pintype "passive"))
      (node (ref "SW1") (pin "3") (pinfunction "3_3") (pintype "passive"))
    )
    (net (code "63") (name "Net-(C14-Pad1)") (class "Default")
      (node (ref "C14") (pin "1") (pinfunction "1_1") (pintype "passive"))
      (node (ref "C20") (pin "1") (pinfunction "1_1") (pintype "passive"))
      (node (ref "SJ3") (pin "2") (pinfunction "2_2") (pintype "passive"))
      (node (ref "U4") (pin "15") (pinfunction "VCCIO2_15") (pintype "bidirectional"))
      (node (ref "U4") (pin "7") (pinfunction "VCCIO2_7") (pintype "bidirectional"))
    )
    (net (code "64") (name "Net-(C16-Pad1)") (class "Default")
      (node (ref "C16") (pin "1") (pinfunction "1_1") (pintype "passive"))
      (node (ref "C19") (pin "1") (pinfunction "1_1") (pintype "passive"))
      (node (ref "SJ1") (pin "2") (pinfunction "2_2") (pintype "passive"))
      (node (ref "U4") (pin "24") (pinfunction "VCCIO0_24") (pintype "bidirectional"))
      (node (ref "U4") (pin "31") (pinfunction "VCCIO0_31") (pintype "bidirectional"))
    )
    (net (code "65") (name "Net-(D1-PadC)") (class "Default")
      (node (ref "D1") (pin "C") (pinfunction "C_C") (pintype "passive"))
      (node (ref "R1") (pin "1") (pinfunction "1_1") (pintype "passive"))
    )
    (net (code "66") (name "Net-(D2-PadA)") (class "Default")
      (node (ref "D2") (pin "A") (pinfunction "A_A") (pintype "passive"))
      (node (ref "J1") (pin "VCC") (pinfunction "VCC_VCC") (pintype "passive"))
    )
    (net (code "67") (name "Net-(D4-C)") (class "Default")
      (node (ref "D4") (pin "2") (pinfunction "C_2") (pintype "passive"))
      (node (ref "U1") (pin "1") (pinfunction "VBAT_1") (pintype "power_in"))
    )
    (net (code "68") (name "Net-(D5-DOUT)") (class "Default")
      (node (ref "D5") (pin "2") (pinfunction "DOUT_2") (pintype "output"))
      (node (ref "TP1") (pin "P$1") (pinfunction "P$1_P$1") (pintype "passive"))
    )
    (net (code "69") (name "Net-(J1-PadTXD)") (class "Default")
      (node (ref "J1") (pin "TXD") (pinfunction "TXD_TXD") (pintype "passive"))
      (node (ref "R2") (pin "1") (pinfunction "1_1") (pintype "passive"))
      (node (ref "SW1") (pin "4") (pinfunction "4_4") (pintype "passive"))
    )
    (net (code "70") (name "Net-(J4-Pad7)") (class "Default")
      (node (ref "J4") (pin "7") (pinfunction "7_7") (pintype "bidirectional"))
      (node (ref "R23") (pin "2") (pinfunction "2_2") (pintype "passive"))
    )
    (net (code "71") (name "Net-(Q1-C1)") (class "Default")
      (node (ref "C1") (pin "2") (pinfunction "2_2") (pintype "passive"))
      (node (ref "Q1") (pin "1") (pinfunction "C1_1") (pintype "passive"))
      (node (ref "R3") (pin "1") (pinfunction "1_1") (pintype "passive"))
    )
    (net (code "72") (name "Net-(Q1-C2)") (class "Default")
      (node (ref "C2") (pin "2") (pinfunction "2_2") (pintype "passive"))
      (node (ref "Q1") (pin "3") (pinfunction "C2_3") (pintype "passive"))
      (node (ref "U1") (pin "5") (pinfunction "PF0-OSC_IN_5") (pintype "bidirectional"))
    )
    (net (code "73") (name "Net-(Q2-D)") (class "Default")
      (node (ref "Q2") (pin "3") (pinfunction "D_3") (pintype "passive"))
      (node (ref "R21") (pin "2") (pinfunction "2_2") (pintype "passive"))
      (node (ref "SJ15") (pin "2") (pinfunction "2_2") (pintype "passive"))
      (node (ref "U4") (pin "26") (pinfunction "JTAGENB/PT15C_26") (pintype "bidirectional"))
    )
    (net (code "74") (name "Net-(Q2-G)") (class "Default")
      (node (ref "J4") (pin "3") (pinfunction "3_3") (pintype "power_in"))
      (node (ref "Q2") (pin "1") (pinfunction "G_1") (pintype "passive"))
      (node (ref "R22") (pin "2") (pinfunction "2_2") (pintype "passive"))
    )
    (net (code "75") (name "Net-(U1A-PF1-OSC_OUT)") (class "Default")
      (node (ref "R3") (pin "2") (pinfunction "2_2") (pintype "passive"))
      (node (ref "U1") (pin "6") (pinfunction "PF1-OSC_OUT_6") (pintype "bidirectional"))
    )
    (net (code "76") (name "Net-(U1C-PB0-ADC_IN8)") (class "Default")
      (node (ref "R12") (pin "2") (pinfunction "2_2") (pintype "passive"))
      (node (ref "U1") (pin "26") (pinfunction "PB0-ADC_IN8_26") (pintype "bidirectional"))
    )
    (net (code "77") (name "Net-(U1C-PB8)") (class "Default")
      (node (ref "R11") (pin "2") (pinfunction "2_2") (pintype "passive"))
      (node (ref "U1") (pin "61") (pinfunction "PB8_61") (pintype "bidirectional"))
    )
    (net (code "78") (name "Net-(U1C-PB10)") (class "Default")
      (node (ref "R13") (pin "2") (pinfunction "2_2") (pintype "passive"))
      (node (ref "U1") (pin "29") (pinfunction "PB10_29") (pintype "bidirectional"))
    )
    (net (code "79") (name "Net-(U1C-PB11)") (class "Default")
      (node (ref "R14") (pin "2") (pinfunction "2_2") (pintype "passive"))
      (node (ref "U1") (pin "30") (pinfunction "PB11_30") (pintype "bidirectional"))
    )
    (net (code "80") (name "Net-(U1E-PF4)") (class "Default")
      (node (ref "R15") (pin "2") (pinfunction "2_2") (pintype "passive"))
      (node (ref "SJ18") (pin "2") (pinfunction "2_2") (pintype "passive"))
      (node (ref "U1") (pin "18") (pinfunction "PF4_18") (pintype "bidirectional"))
    )
    (net (code "81") (name "Net-(U1E-PF5)") (class "Default")
      (node (ref "R16") (pin "2") (pinfunction "2_2") (pintype "passive"))
      (node (ref "SJ17") (pin "2") (pinfunction "2_2") (pintype "passive"))
      (node (ref "U1") (pin "19") (pinfunction "PF5_19") (pintype "bidirectional"))
    )
    (net (code "82") (name "Net-(U1E-PF6)") (class "Default")
      (node (ref "R17") (pin "2") (pinfunction "2_2") (pintype "passive"))
      (node (ref "SJ6") (pin "2") (pinfunction "2_2") (pintype "passive"))
      (node (ref "U1") (pin "47") (pinfunction "PF6_47") (pintype "bidirectional"))
    )
    (net (code "83") (name "Net-(U1E-PF7)") (class "Default")
      (node (ref "R10") (pin "2") (pinfunction "2_2") (pintype "passive"))
      (node (ref "R18") (pin "2") (pinfunction "2_2") (pintype "passive"))
      (node (ref "SJ5") (pin "2") (pinfunction "2_2") (pintype "passive"))
      (node (ref "U1") (pin "48") (pinfunction "PF7_48") (pintype "bidirectional"))
    )
    (net (code "84") (name "Net-(U1F-VDDA)") (class "Default")
      (node (ref "C10") (pin "1") (pinfunction "1_1") (pintype "passive"))
      (node (ref "C11") (pin "1") (pinfunction "1_1") (pintype "passive"))
      (node (ref "FB1") (pin "1") (pinfunction "1_1") (pintype "passive"))
      (node (ref "R5") (pin "2") (pinfunction "2_2") (pintype "passive"))
      (node (ref "U1") (pin "13") (pinfunction "VDDA_13") (pintype "power_in"))
    )
    (net (code "85") (name "Net-(U1F-VSSA)") (class "Default")
      (node (ref "C10") (pin "2") (pinfunction "2_2") (pintype "passive"))
      (node (ref "C11") (pin "2") (pinfunction "2_2") (pintype "passive"))
      (node (ref "FB2") (pin "1") (pinfunction "1_1") (pintype "passive"))
      (node (ref "U1") (pin "12") (pinfunction "VSSA_12") (pintype "power_in"))
    )
    (net (code "86") (name "Net-(U4A-DONE{slash}PT17D)") (class "Default")
      (node (ref "SJ8") (pin "2") (pinfunction "2_2") (pintype "passive"))
      (node (ref "U4") (pin "23") (pinfunction "DONE/PT17D_23") (pintype "bidirectional"))
    )
    (net (code "87") (name "Net-(U4B-PB_4A{slash}6C{slash}9A{slash}11A{slash}13A)") (class "Default")
      (node (ref "SJ9") (pin "2") (pinfunction "2_2") (pintype "passive"))
      (node (ref "U4") (pin "11") (pinfunction "PB_4A/6C/9A/11A/13A_11") (pintype "bidirectional"))
    )
    (net (code "88") (name "Net-(U4B-PB_4B{slash}6D{slash}9B{slash}11B{slash}13B)") (class "Default")
      (node (ref "SJ10") (pin "2") (pinfunction "2_2") (pintype "passive"))
      (node (ref "U4") (pin "12") (pinfunction "PB_4B/6D/9B/11B/13B_12") (pintype "bidirectional"))
    )
    (net (code "89") (name "Net-(U4B-PB_4C{slash}10C{slash}11A{slash}16A{slash}20A)") (class "Default")
      (node (ref "SJ11") (pin "2") (pinfunction "2_2") (pintype "passive"))
      (node (ref "U4") (pin "13") (pinfunction "PB_4C/10C/11A/16A/20A_13") (pintype "bidirectional"))
    )
    (net (code "90") (name "Net-(U4B-PB_4D{slash}10D{slash}11B{slash}16B{slash}20B)") (class "Default")
      (node (ref "SJ12") (pin "2") (pinfunction "2_2") (pintype "passive"))
      (node (ref "U4") (pin "14") (pinfunction "PB_4D/10D/11B/16B/20B_14") (pintype "bidirectional"))
    )
    (net (code "91") (name "Net-(U4B-PL_5C{slash}7A{slash}9A{slash}12A{slash}17A)") (class "Default")
      (node (ref "SJ13") (pin "2") (pinfunction "2_2") (pintype "passive"))
      (node (ref "U4") (pin "4") (pinfunction "PL_5C/7A/9A/12A/17A_4") (pintype "bidirectional"))
    )
    (net (code "92") (name "Net-(U4B-PL_5D{slash}7B{slash}9B{slash}12B{slash}17B)") (class "Default")
      (node (ref "SJ14") (pin "2") (pinfunction "2_2") (pintype "passive"))
      (node (ref "U4") (pin "5") (pinfunction "PL_5D/7B/9B/12B/17B_5") (pintype "bidirectional"))
    )
    (net (code "93") (name "Net-(U4B-PR_5B{slash}5D{slash}5D{slash}7B{slash}10B)") (class "Default")
      (node (ref "SJ7") (pin "2") (pinfunction "2_2") (pintype "passive"))
      (node (ref "U4") (pin "20") (pinfunction "PR_5B/5D/5D/7B/10B_20") (pintype "bidirectional"))
    )
    (net (code "94") (name "Net-(U4C-VCCIO1)") (class "Default")
      (node (ref "C15") (pin "1") (pinfunction "1_1") (pintype "passive"))
      (node (ref "SJ2") (pin "2") (pinfunction "2_2") (pintype "passive"))
      (node (ref "U4") (pin "19") (pinfunction "VCCIO1_19") (pintype "bidirectional"))
    )
    (net (code "95") (name "Net-(U4C-VCCIO3)") (class "Default")
      (node (ref "C13") (pin "1") (pinfunction "1_1") (pintype "passive"))
      (node (ref "SJ4") (pin "2") (pinfunction "2_2") (pintype "passive"))
      (node (ref "U4") (pin "6") (pinfunction "VCCIO3_6") (pintype "bidirectional"))
    )
    (net (code "96") (name "OSC32_IN") (class "Default")
      (node (ref "C8") (pin "2") (pinfunction "2_2") (pintype "passive"))
      (node (ref "U1") (pin "3") (pinfunction "PC14-OSC32_IN_3") (pintype "bidirectional"))
      (node (ref "Y1") (pin "X2") (pinfunction "2_X2") (pintype "passive"))
    )
    (net (code "97") (name "OSC32_OUT") (class "Default")
      (node (ref "C9") (pin "2") (pinfunction "2_2") (pintype "passive"))
      (node (ref "U1") (pin "4") (pinfunction "PC15-OSC32_OUT_4") (pintype "bidirectional"))
      (node (ref "Y1") (pin "X1") (pinfunction "1_X1") (pintype "passive"))
    )
    (net (code "98") (name "PA7") (class "Default")
      (node (ref "D5") (pin "4") (pinfunction "DIN_4") (pintype "input"))
      (node (ref "U1") (pin "23") (pinfunction "PA7-ADC_IN7_23") (pintype "bidirectional"))
    )
    (net (code "99") (name "RSV0") (class "Default")
      (node (ref "EXB1") (pin "20") (pinfunction "RSV0_20") (pintype "passive"))
      (node (ref "EXT1") (pin "20") (pinfunction "RSV0_20") (pintype "passive"))
    )
    (net (code "100") (name "RSV1") (class "Default")
      (node (ref "EXB1") (pin "18") (pinfunction "RSV1_18") (pintype "passive"))
      (node (ref "EXT1") (pin "18") (pinfunction "RSV1_18") (pintype "passive"))
    )
    (net (code "101") (name "RSV2") (class "Default")
      (node (ref "EXB1") (pin "16") (pinfunction "RSV2_16") (pintype "passive"))
      (node (ref "EXT1") (pin "16") (pinfunction "RSV2_16") (pintype "passive"))
    )
    (net (code "102") (name "VBATT") (class "Default")
      (node (ref "D4") (pin "1") (pinfunction "A_1") (pintype "passive"))
      (node (ref "EXB1") (pin "4") (pinfunction "VBATT_4") (pintype "power_in"))
      (node (ref "EXT1") (pin "4") (pinfunction "VBATT_4") (pintype "power_in"))
    )
    (net (code "103") (name "VCCIO") (class "Default")
      (node (ref "EXB1") (pin "2") (pinfunction "VCC(IO)_2") (pintype "power_in"))
      (node (ref "EXT1") (pin "2") (pinfunction "VCC(IO)_2") (pintype "power_in"))
      (node (ref "R10") (pin "1") (pinfunction "1_1") (pintype "passive"))
      (node (ref "SJ1") (pin "3") (pinfunction "3_3") (pintype "passive"))
      (node (ref "SJ16") (pin "1") (pinfunction "1_1") (pintype "passive"))
      (node (ref "SJ2") (pin "3") (pinfunction "3_3") (pintype "passive"))
      (node (ref "SJ3") (pin "3") (pinfunction "3_3") (pintype "passive"))
      (node (ref "SJ4") (pin "3") (pinfunction "3_3") (pintype "passive"))
      (node (ref "TP5") (pin "P$1") (pinfunction "P$1_P$1") (pintype "passive"))
    )
    (net (code "104") (name "VIN") (class "Default")
      (node (ref "EXB1") (pin "10") (pinfunction "VIN_10") (pintype "power_in"))
      (node (ref "EXT1") (pin "10") (pinfunction "VIN_10") (pintype "power_in"))
    )
    (net (code "105") (name "unconnected-(OLPADS1-2-PadP$2)") (class "Default")
      (node (ref "OLPADS1") (pin "P$2") (pinfunction "2_P$2") (pintype "passive"))
    )
    (net (code "106") (name "unconnected-(OLPADS1-Pad1)") (class "Default")
      (node (ref "OLPADS1") (pin "1") (pinfunction "1_1") (pintype "passive"))
    )
    (net (code "107") (name "unconnected-(OLPADS1-Pad3)") (class "Default")
      (node (ref "OLPADS1") (pin "3") (pinfunction "3_3") (pintype "passive"))
    )
    (net (code "108") (name "unconnected-(OLPADS1-Pad4)") (class "Default")
      (node (ref "OLPADS1") (pin "4") (pinfunction "4_4") (pintype "passive"))
    )
    (net (code "109") (name "unconnected-(OLPADS1-Pad5)") (class "Default")
      (node (ref "OLPADS1") (pin "5") (pinfunction "5_5") (pintype "passive"))
    )
    (net (code "110") (name "unconnected-(OLPADS1-Pad6)") (class "Default")
      (node (ref "OLPADS1") (pin "6") (pinfunction "6_6") (pintype "passive"))
    )
    (net (code "111") (name "unconnected-(OLPADS1-Pad7)") (class "Default")
      (node (ref "OLPADS1") (pin "7") (pinfunction "7_7") (pintype "passive"))
    )
    (net (code "112") (name "unconnected-(OLPADS1-Pad8)") (class "Default")
      (node (ref "OLPADS1") (pin "8") (pinfunction "8_8") (pintype "passive"))
    )
    (net (code "113") (name "unconnected-(OLPADS1-Pad9)") (class "Default")
      (node (ref "OLPADS1") (pin "9") (pinfunction "9_9") (pintype "passive"))
    )
    (net (code "114") (name "unconnected-(OLPADS2-2-PadP$2)") (class "Default")
      (node (ref "OLPADS2") (pin "P$2") (pinfunction "2_P$2") (pintype "passive"))
    )
    (net (code "115") (name "unconnected-(OLPADS2-Pad1)") (class "Default")
      (node (ref "OLPADS2") (pin "1") (pinfunction "1_1") (pintype "passive"))
    )
    (net (code "116") (name "unconnected-(OLPADS2-Pad3)") (class "Default")
      (node (ref "OLPADS2") (pin "3") (pinfunction "3_3") (pintype "passive"))
    )
    (net (code "117") (name "unconnected-(OLPADS2-Pad4)") (class "Default")
      (node (ref "OLPADS2") (pin "4") (pinfunction "4_4") (pintype "passive"))
    )
    (net (code "118") (name "unconnected-(OLPADS2-Pad5)") (class "Default")
      (node (ref "OLPADS2") (pin "5") (pinfunction "5_5") (pintype "passive"))
    )
    (net (code "119") (name "unconnected-(OLPADS2-Pad6)") (class "Default")
      (node (ref "OLPADS2") (pin "6") (pinfunction "6_6") (pintype "passive"))
    )
    (net (code "120") (name "unconnected-(OLPADS2-Pad7)") (class "Default")
      (node (ref "OLPADS2") (pin "7") (pinfunction "7_7") (pintype "passive"))
    )
    (net (code "121") (name "unconnected-(OLPADS2-Pad8)") (class "Default")
      (node (ref "OLPADS2") (pin "8") (pinfunction "8_8") (pintype "passive"))
    )
    (net (code "122") (name "unconnected-(OLPADS2-Pad9)") (class "Default")
      (node (ref "OLPADS2") (pin "9") (pinfunction "9_9") (pintype "passive"))
    )
    (net (code "123") (name "unconnected-(OLPADS2-Pad10)") (class "Default")
      (node (ref "OLPADS2") (pin "10") (pinfunction "10_10") (pintype "passive"))
    )
    (net (code "124") (name "unconnected-(U4A-INITN{slash}PT17C-PadNC1)") (class "Default")
      (node (ref "U4") (pin "NC1") (pinfunction "INITN/PT17C_NC1") (pintype "bidirectional"))
    )
    (net (code "125") (name "unconnected-(U4A-PB_2B{slash}4B{slash}4D{slash}5B{slash}4B-PadNC2)") (class "Default")
      (node (ref "U4") (pin "NC2") (pinfunction "PB_2B/4B/4D/5B/4B_NC2") (pintype "bidirectional"))
    )
    (net (code "126") (name "unconnected-(X1-KL1-Pad1)") (class "Default")
      (node (ref "X1") (pin "1") (pinfunction "KL1_1") (pintype "passive"))
    )
    (net (code "127") (name "unconnected-(X2-KL1-Pad1)") (class "Default")
      (node (ref "X2") (pin "1") (pinfunction "KL1_1") (pintype "passive"))
    )
    (net (code "128") (name "unconnected-(X3-KL1-Pad1)") (class "Default")
      (node (ref "X3") (pin "1") (pinfunction "KL1_1") (pintype "passive"))
    )
    (net (code "129") (name "unconnected-(X4-KL1-Pad1)") (class "Default")
      (node (ref "X4") (pin "1") (pinfunction "KL1_1") (pintype "passive"))
    )
  )
)
